# ModuleCarrier-MTS-Dragonfly.net
KiCad netlist of a schematic drawn in EAGLE
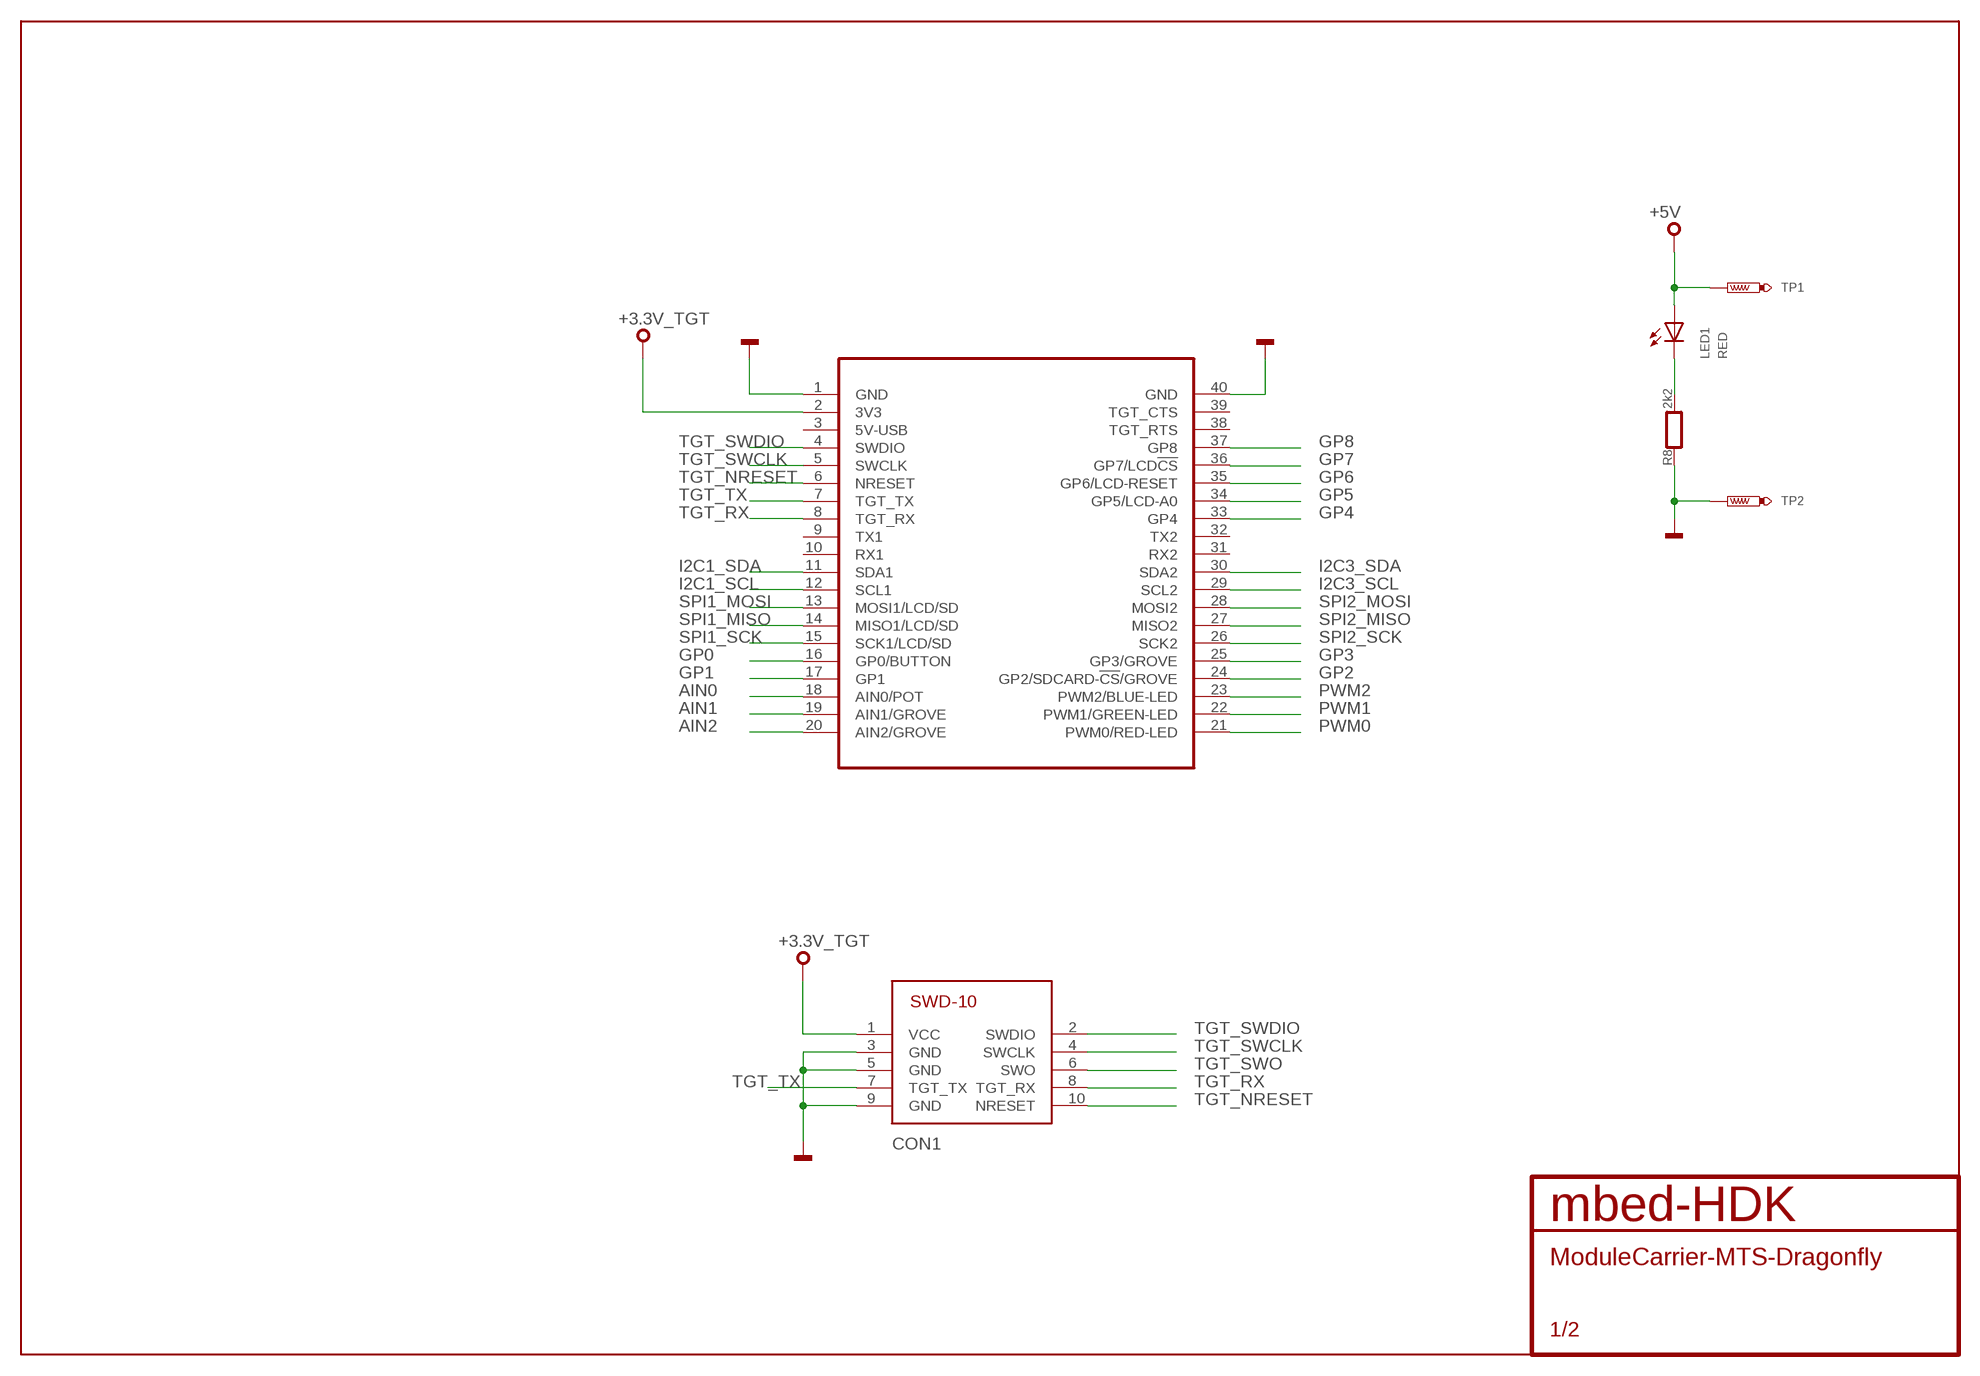
[diagram p0: schematic, sheet 1]
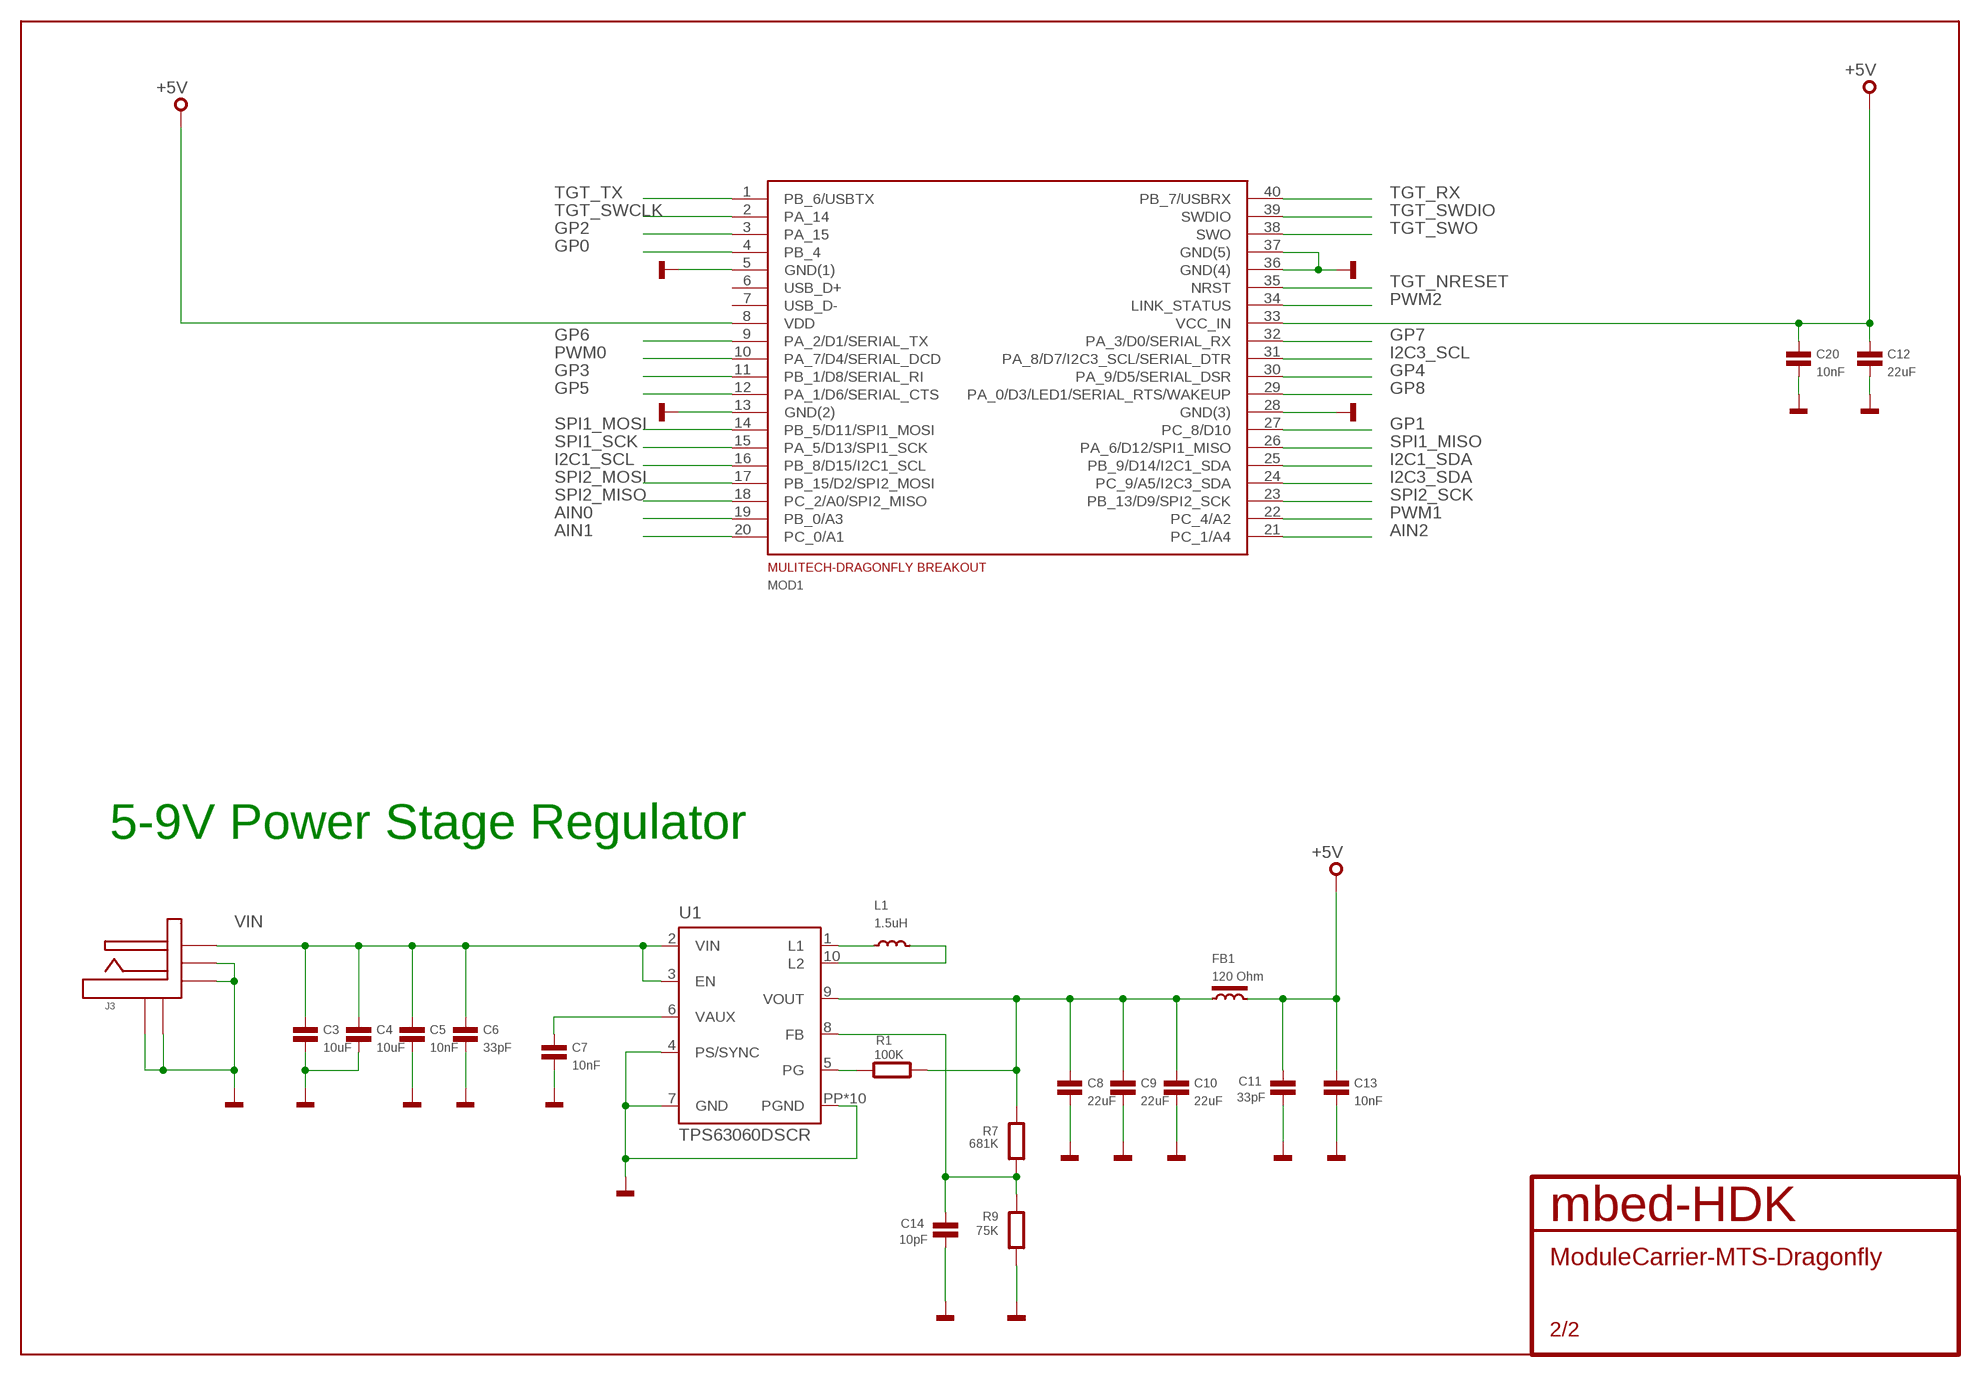
[diagram p1: schematic, sheet 2]

(export (version "E")
  (design (tool "Eeschema 10.0.6"))
  (components
    (comp (ref "C3")
      (value "10uF")
      (footprint "eagle-import:0603")
      (libsource (lib "eagle-import") (part "CAPACITOR0603"))
    )
    (comp (ref "C4")
      (value "10uF")
      (footprint "eagle-import:0603")
      (libsource (lib "eagle-import") (part "CAPACITOR0603"))
    )
    (comp (ref "C5")
      (value "10nF")
      (footprint "eagle-import:0603")
      (libsource (lib "eagle-import") (part "CAPACITOR0603"))
    )
    (comp (ref "C6")
      (value "33pF")
      (footprint "eagle-import:0603")
      (libsource (lib "eagle-import") (part "CAPACITOR0603"))
    )
    (comp (ref "C7")
      (value "10nF")
      (footprint "eagle-import:0603")
      (libsource (lib "eagle-import") (part "CAPACITOR0603"))
    )
    (comp (ref "C8")
      (value "22uF")
      (footprint "eagle-import:0603")
      (libsource (lib "eagle-import") (part "CAPACITOR0603"))
    )
    (comp (ref "C9")
      (value "22uF")
      (footprint "eagle-import:0603")
      (libsource (lib "eagle-import") (part "CAPACITOR0603"))
    )
    (comp (ref "C10")
      (value "22uF")
      (footprint "eagle-import:0603")
      (libsource (lib "eagle-import") (part "CAPACITOR0603"))
    )
    (comp (ref "C11")
      (value "33pF")
      (footprint "eagle-import:0603")
      (libsource (lib "eagle-import") (part "CAPACITOR0603"))
    )
    (comp (ref "C12")
      (value "22uF")
      (footprint "eagle-import:0603")
      (libsource (lib "eagle-import") (part "CAPACITOR0603"))
    )
    (comp (ref "C13")
      (value "10nF")
      (footprint "eagle-import:0603")
      (libsource (lib "eagle-import") (part "CAPACITOR0603"))
    )
    (comp (ref "C14")
      (value "10pF")
      (footprint "eagle-import:0603")
      (libsource (lib "eagle-import") (part "CAPACITOR0603"))
    )
    (comp (ref "C20")
      (value "10nF")
      (footprint "eagle-import:0603")
      (libsource (lib "eagle-import") (part "CAPACITOR0603"))
    )
    (comp (ref "FB1")
      (value "120 Ohm")
      (footprint "eagle-import:0603")
      (libsource (lib "eagle-import") (part "FERRITE0603"))
    )
    (comp (ref "J3")
      (value "FC68145S")
      (footprint "eagle-import:FC68145S")
      (libsource (lib "eagle-import") (part "FC68145S"))
    )
    (comp (ref "L1")
      (value "1.5uH")
      (footprint "eagle-import:XFL4020-472MEC")
      (libsource (lib "eagle-import") (part "INDUCTORXFL4020"))
    )
    (comp (ref "MOD1")
      (value "MULITECH-DRAGONFLY-BREAKOUT")
      (footprint "eagle-import:MULITECH-DRAGONFLY-BREAKOUT")
      (fields (field (name "MF") "Hirose"))
      (libsource (lib "eagle-import") (part "MULITECH-DRAGONFLY-BREAKOUT"))
    )
    (comp (ref "R1")
      (value "100K")
      (footprint "eagle-import:0402")
      (libsource (lib "eagle-import") (part "mbed-HDK-RLCQ_RESISTOR0402"))
    )
    (comp (ref "R7")
      (value "681K")
      (footprint "eagle-import:0402")
      (libsource (lib "eagle-import") (part "mbed-HDK-RLCQ_RESISTOR0402"))
    )
    (comp (ref "R9")
      (value "75K")
      (footprint "eagle-import:0402")
      (libsource (lib "eagle-import") (part "mbed-HDK-RLCQ_RESISTOR0402"))
    )
    (comp (ref "U1")
      (value "TPS63060DSCR")
      (footprint "eagle-import:DSC-S-PWSON-N10")
      (fields (field (name "MF") "TEXAS INSTRUMENTS"))
      (libsource (lib "eagle-import") (part "TPS63060DSCR"))
    )
    (comp (ref "CON1")
      (value "SWD-10/TC2050_SMD")
      (footprint "eagle-import:FTSH-105-02")
      (libsource (lib "eagle-import") (part "SWD-10/TC2050_SMD"))
    )
    (comp (ref "LED1")
      (value "RED")
      (footprint "eagle-import:CHIPLED_0603")
      (fields (field (name "MF") "Wurth Electronics Inc"))
      (libsource (lib "eagle-import") (part "SMD_LED0603"))
    )
    (comp (ref "MOD2")
      (value "MODULE_DAUGHTER")
      (footprint "eagle-import:MODULE_DAUGHTER")
      (libsource (lib "eagle-import") (part "MODULE_DAUGHTER"))
    )
    (comp (ref "R8")
      (value "2k2")
      (footprint "eagle-import:0603")
      (libsource (lib "eagle-import") (part "RESISTOR0603"))
    )
    (comp (ref "TP1")
      (value "TEST-POINT-50R-PTH")
      (footprint "eagle-import:TP50-PTH")
      (libsource (lib "eagle-import") (part "TEST-POINT-50R-PTH"))
    )
    (comp (ref "TP2")
      (value "TEST-POINT-50R-PTH")
      (footprint "eagle-import:TP50-PTH")
      (libsource (lib "eagle-import") (part "TEST-POINT-50R-PTH"))
    )
  )
  (nets
    (net (code "1") (name "+3.3V_TGT") (class "Default")
      (node (ref "CON1") (pin "1") (pinfunction "VCC_1") (pintype "bidirectional"))
      (node (ref "MOD2") (pin "2") (pinfunction "3V3_2") (pintype "bidirectional"))
    )
    (net (code "2") (name "+5V") (class "Default")
      (node (ref "C11") (pin "1") (pinfunction "P$1_1") (pintype "passive"))
      (node (ref "C12") (pin "1") (pinfunction "P$1_1") (pintype "passive"))
      (node (ref "C13") (pin "1") (pinfunction "P$1_1") (pintype "passive"))
      (node (ref "C20") (pin "1") (pinfunction "P$1_1") (pintype "passive"))
      (node (ref "FB1") (pin "2") (pinfunction "P$2_2") (pintype "bidirectional"))
      (node (ref "LED1") (pin "A") (pinfunction "A_A") (pintype "passive"))
      (node (ref "MOD1") (pin "33") (pinfunction "VCC_IN_33") (pintype "bidirectional"))
      (node (ref "MOD1") (pin "8") (pinfunction "VDD_8") (pintype "bidirectional"))
      (node (ref "TP1") (pin "TP") (pinfunction "TP_TP") (pintype "input"))
    )
    (net (code "3") (name "AIN0") (class "Default")
      (node (ref "MOD1") (pin "19") (pinfunction "PB_0/A3_19") (pintype "bidirectional"))
      (node (ref "MOD2") (pin "18") (pinfunction "AIN0/POT_18") (pintype "bidirectional"))
    )
    (net (code "4") (name "AIN1") (class "Default")
      (node (ref "MOD1") (pin "20") (pinfunction "PC_0/A1_20") (pintype "bidirectional"))
      (node (ref "MOD2") (pin "19") (pinfunction "AIN1/GROVE_19") (pintype "bidirectional"))
    )
    (net (code "5") (name "AIN2") (class "Default")
      (node (ref "MOD1") (pin "21") (pinfunction "PC_1/A4_21") (pintype "bidirectional"))
      (node (ref "MOD2") (pin "20") (pinfunction "AIN2/GROVE_20") (pintype "bidirectional"))
    )
    (net (code "6") (name "GND") (class "Default")
      (node (ref "C10") (pin "2") (pinfunction "P$2_2") (pintype "passive"))
      (node (ref "C11") (pin "2") (pinfunction "P$2_2") (pintype "passive"))
      (node (ref "C12") (pin "2") (pinfunction "P$2_2") (pintype "passive"))
      (node (ref "C13") (pin "2") (pinfunction "P$2_2") (pintype "passive"))
      (node (ref "C14") (pin "2") (pinfunction "P$2_2") (pintype "passive"))
      (node (ref "C20") (pin "2") (pinfunction "P$2_2") (pintype "passive"))
      (node (ref "C3") (pin "2") (pinfunction "P$2_2") (pintype "passive"))
      (node (ref "C4") (pin "2") (pinfunction "P$2_2") (pintype "passive"))
      (node (ref "C5") (pin "2") (pinfunction "P$2_2") (pintype "passive"))
      (node (ref "C6") (pin "2") (pinfunction "P$2_2") (pintype "passive"))
      (node (ref "C7") (pin "2") (pinfunction "P$2_2") (pintype "passive"))
      (node (ref "C8") (pin "2") (pinfunction "P$2_2") (pintype "passive"))
      (node (ref "C9") (pin "2") (pinfunction "P$2_2") (pintype "passive"))
      (node (ref "CON1") (pin "3") (pinfunction "GND_3") (pintype "bidirectional"))
      (node (ref "CON1") (pin "5") (pinfunction "GND_5") (pintype "bidirectional"))
      (node (ref "CON1") (pin "9") (pinfunction "GND_9") (pintype "bidirectional"))
      (node (ref "J3") (pin "CASE1") (pinfunction "CASE1_CASE1") (pintype "bidirectional"))
      (node (ref "J3") (pin "P$5") (pinfunction "CASE2_P$5") (pintype "bidirectional"))
      (node (ref "J3") (pin "SHUNT") (pinfunction "SWITCHED_SHUNT") (pintype "bidirectional"))
      (node (ref "J3") (pin "SLEEVE") (pinfunction "SLEEVE_SLEEVE") (pintype "bidirectional"))
      (node (ref "MOD1") (pin "13") (pinfunction "GND(2)_13") (pintype "bidirectional"))
      (node (ref "MOD1") (pin "28") (pinfunction "GND(3)_28") (pintype "bidirectional"))
      (node (ref "MOD1") (pin "36") (pinfunction "GND(4)_36") (pintype "bidirectional"))
      (node (ref "MOD1") (pin "37") (pinfunction "GND(5)_37") (pintype "bidirectional"))
      (node (ref "MOD1") (pin "5") (pinfunction "GND(1)_5") (pintype "bidirectional"))
      (node (ref "MOD2") (pin "1") (pinfunction "GND_1") (pintype "bidirectional"))
      (node (ref "MOD2") (pin "40") (pinfunction "GND_40") (pintype "bidirectional"))
      (node (ref "R8") (pin "1") (pinfunction "P$1_1") (pintype "passive"))
      (node (ref "R9") (pin "1") (pinfunction "P$1_1") (pintype "passive"))
      (node (ref "TP2") (pin "TP") (pinfunction "TP_TP") (pintype "input"))
      (node (ref "U1") (pin "4") (pinfunction "PS/SYNC_4") (pintype "input"))
      (node (ref "U1") (pin "7") (pinfunction "GND_7") (pintype "input"))
      (node (ref "U1") (pin "PP") (pinfunction "PGND_PP") (pintype "power_in"))
      (node (ref "U1") (pin "PP@1") (pinfunction "PGND_PP@1") (pintype "power_in"))
      (node (ref "U1") (pin "PP@10") (pinfunction "PGND_PP@10") (pintype "power_in"))
      (node (ref "U1") (pin "PP@2") (pinfunction "PGND_PP@2") (pintype "power_in"))
      (node (ref "U1") (pin "PP@3") (pinfunction "PGND_PP@3") (pintype "power_in"))
      (node (ref "U1") (pin "PP@4") (pinfunction "PGND_PP@4") (pintype "power_in"))
      (node (ref "U1") (pin "PP@5") (pinfunction "PGND_PP@5") (pintype "power_in"))
      (node (ref "U1") (pin "PP@7") (pinfunction "PGND_PP@7") (pintype "power_in"))
      (node (ref "U1") (pin "PP@8") (pinfunction "PGND_PP@8") (pintype "power_in"))
      (node (ref "U1") (pin "PP@9") (pinfunction "PGND_PP@9") (pintype "power_in"))
    )
    (net (code "7") (name "GP0") (class "Default")
      (node (ref "MOD1") (pin "4") (pinfunction "PB_4_4") (pintype "bidirectional"))
      (node (ref "MOD2") (pin "16") (pinfunction "GP0/BUTTON_16") (pintype "bidirectional"))
    )
    (net (code "8") (name "GP1") (class "Default")
      (node (ref "MOD1") (pin "27") (pinfunction "PC_8/D10_27") (pintype "bidirectional"))
      (node (ref "MOD2") (pin "17") (pinfunction "GP1_17") (pintype "bidirectional"))
    )
    (net (code "9") (name "GP2") (class "Default")
      (node (ref "MOD1") (pin "3") (pinfunction "PA_15_3") (pintype "bidirectional"))
      (node (ref "MOD2") (pin "24") (pinfunction "GP2/SDCARD-~{CS}/GROVE_24") (pintype "bidirectional"))
    )
    (net (code "10") (name "GP3") (class "Default")
      (node (ref "MOD1") (pin "11") (pinfunction "PB_1/D8/SERIAL_RI_11") (pintype "bidirectional"))
      (node (ref "MOD2") (pin "25") (pinfunction "GP3/GROVE_25") (pintype "bidirectional"))
    )
    (net (code "11") (name "GP4") (class "Default")
      (node (ref "MOD1") (pin "30") (pinfunction "PA_9/D5/SERIAL_DSR_30") (pintype "bidirectional"))
      (node (ref "MOD2") (pin "33") (pinfunction "GP4_33") (pintype "bidirectional"))
    )
    (net (code "12") (name "GP5") (class "Default")
      (node (ref "MOD1") (pin "12") (pinfunction "PA_1/D6/SERIAL_CTS_12") (pintype "bidirectional"))
      (node (ref "MOD2") (pin "34") (pinfunction "GP5/LCD-A0_34") (pintype "bidirectional"))
    )
    (net (code "13") (name "GP6") (class "Default")
      (node (ref "MOD1") (pin "9") (pinfunction "PA_2/D1/SERIAL_TX_9") (pintype "bidirectional"))
      (node (ref "MOD2") (pin "35") (pinfunction "GP6/LCD-RESET_35") (pintype "bidirectional"))
    )
    (net (code "14") (name "GP7") (class "Default")
      (node (ref "MOD1") (pin "32") (pinfunction "PA_3/D0/SERIAL_RX_32") (pintype "bidirectional"))
      (node (ref "MOD2") (pin "36") (pinfunction "GP7/LCD~{CS}_36") (pintype "bidirectional"))
    )
    (net (code "15") (name "GP8") (class "Default")
      (node (ref "MOD1") (pin "29") (pinfunction "PA_0/D3/LED1/SERIAL_RTS/WAKEUP_29") (pintype "bidirectional"))
      (node (ref "MOD2") (pin "37") (pinfunction "GP8_37") (pintype "bidirectional"))
    )
    (net (code "16") (name "I2C1_SCL") (class "Default")
      (node (ref "MOD1") (pin "16") (pinfunction "PB_8/D15/I2C1_SCL_16") (pintype "bidirectional"))
      (node (ref "MOD2") (pin "12") (pinfunction "SCL1_12") (pintype "bidirectional"))
    )
    (net (code "17") (name "I2C1_SDA") (class "Default")
      (node (ref "MOD1") (pin "25") (pinfunction "PB_9/D14/I2C1_SDA_25") (pintype "bidirectional"))
      (node (ref "MOD2") (pin "11") (pinfunction "SDA1_11") (pintype "bidirectional"))
    )
    (net (code "18") (name "I2C3_SCL") (class "Default")
      (node (ref "MOD1") (pin "31") (pinfunction "PA_8/D7/I2C3_SCL/SERIAL_DTR_31") (pintype "bidirectional"))
      (node (ref "MOD2") (pin "29") (pinfunction "SCL2_29") (pintype "bidirectional"))
    )
    (net (code "19") (name "I2C3_SDA") (class "Default")
      (node (ref "MOD1") (pin "24") (pinfunction "PC_9/A5/I2C3_SDA_24") (pintype "bidirectional"))
      (node (ref "MOD2") (pin "30") (pinfunction "SDA2_30") (pintype "bidirectional"))
    )
    (net (code "20") (name "Net-(C7-P$1)") (class "Default")
      (node (ref "C7") (pin "1") (pinfunction "P$1_1") (pintype "passive"))
      (node (ref "U1") (pin "6") (pinfunction "VAUX_6") (pintype "power_in"))
    )
    (net (code "21") (name "Net-(C10-P$1)") (class "Default")
      (node (ref "C10") (pin "1") (pinfunction "P$1_1") (pintype "passive"))
      (node (ref "C8") (pin "1") (pinfunction "P$1_1") (pintype "passive"))
      (node (ref "C9") (pin "1") (pinfunction "P$1_1") (pintype "passive"))
      (node (ref "FB1") (pin "1") (pinfunction "P$1_1") (pintype "bidirectional"))
      (node (ref "R1") (pin "2") (pinfunction "P$2_2") (pintype "passive"))
      (node (ref "R7") (pin "2") (pinfunction "P$2_2") (pintype "passive"))
      (node (ref "U1") (pin "9") (pinfunction "VOUT_9") (pintype "output"))
    )
    (net (code "22") (name "Net-(C14-P$1)") (class "Default")
      (node (ref "C14") (pin "1") (pinfunction "P$1_1") (pintype "passive"))
      (node (ref "R7") (pin "1") (pinfunction "P$1_1") (pintype "passive"))
      (node (ref "R9") (pin "2") (pinfunction "P$2_2") (pintype "passive"))
      (node (ref "U1") (pin "8") (pinfunction "FB_8") (pintype "input"))
    )
    (net (code "23") (name "Net-(R1-P$1)") (class "Default")
      (node (ref "R1") (pin "1") (pinfunction "P$1_1") (pintype "passive"))
      (node (ref "U1") (pin "5") (pinfunction "PG_5") (pintype "output"))
    )
    (net (code "24") (name "Net-(R8-P$2)") (class "Default")
      (node (ref "LED1") (pin "C") (pinfunction "C_C") (pintype "passive"))
      (node (ref "R8") (pin "2") (pinfunction "P$2_2") (pintype "passive"))
    )
    (net (code "25") (name "Net-(U1-L1)") (class "Default")
      (node (ref "L1") (pin "P$1") (pinfunction "P$1_P$1") (pintype "bidirectional"))
      (node (ref "U1") (pin "1") (pinfunction "L1_1") (pintype "input"))
    )
    (net (code "26") (name "Net-(U1-L2)") (class "Default")
      (node (ref "L1") (pin "P$2") (pinfunction "P$2_P$2") (pintype "bidirectional"))
      (node (ref "U1") (pin "10") (pinfunction "L2_10") (pintype "input"))
    )
    (net (code "27") (name "PWM0") (class "Default")
      (node (ref "MOD1") (pin "10") (pinfunction "PA_7/D4/SERIAL_DCD_10") (pintype "bidirectional"))
      (node (ref "MOD2") (pin "21") (pinfunction "PWM0/RED-LED_21") (pintype "bidirectional"))
    )
    (net (code "28") (name "PWM1") (class "Default")
      (node (ref "MOD1") (pin "22") (pinfunction "PC_4/A2_22") (pintype "bidirectional"))
      (node (ref "MOD2") (pin "22") (pinfunction "PWM1/GREEN-LED_22") (pintype "bidirectional"))
    )
    (net (code "29") (name "PWM2") (class "Default")
      (node (ref "MOD1") (pin "34") (pinfunction "LINK_STATUS_34") (pintype "bidirectional"))
      (node (ref "MOD2") (pin "23") (pinfunction "PWM2/BLUE-LED_23") (pintype "bidirectional"))
    )
    (net (code "30") (name "SPI1_MISO") (class "Default")
      (node (ref "MOD1") (pin "26") (pinfunction "PA_6/D12/SPI1_MISO_26") (pintype "bidirectional"))
      (node (ref "MOD2") (pin "14") (pinfunction "MISO1/LCD/SD_14") (pintype "bidirectional"))
    )
    (net (code "31") (name "SPI1_MOSI") (class "Default")
      (node (ref "MOD1") (pin "14") (pinfunction "PB_5/D11/SPI1_MOSI_14") (pintype "bidirectional"))
      (node (ref "MOD2") (pin "13") (pinfunction "MOSI1/LCD/SD_13") (pintype "bidirectional"))
    )
    (net (code "32") (name "SPI1_SCK") (class "Default")
      (node (ref "MOD1") (pin "15") (pinfunction "PA_5/D13/SPI1_SCK_15") (pintype "bidirectional"))
      (node (ref "MOD2") (pin "15") (pinfunction "SCK1/LCD/SD_15") (pintype "bidirectional"))
    )
    (net (code "33") (name "SPI2_MISO") (class "Default")
      (node (ref "MOD1") (pin "18") (pinfunction "PC_2/A0/SPI2_MISO_18") (pintype "bidirectional"))
      (node (ref "MOD2") (pin "27") (pinfunction "MISO2_27") (pintype "bidirectional"))
    )
    (net (code "34") (name "SPI2_MOSI") (class "Default")
      (node (ref "MOD1") (pin "17") (pinfunction "PB_15/D2/SPI2_MOSI_17") (pintype "bidirectional"))
      (node (ref "MOD2") (pin "28") (pinfunction "MOSI2_28") (pintype "bidirectional"))
    )
    (net (code "35") (name "SPI2_SCK") (class "Default")
      (node (ref "MOD1") (pin "23") (pinfunction "PB_13/D9/SPI2_SCK_23") (pintype "bidirectional"))
      (node (ref "MOD2") (pin "26") (pinfunction "SCK2_26") (pintype "bidirectional"))
    )
    (net (code "36") (name "TGT_NRESET") (class "Default")
      (node (ref "CON1") (pin "10") (pinfunction "NRESET_10") (pintype "bidirectional"))
      (node (ref "MOD1") (pin "35") (pinfunction "NRST_35") (pintype "bidirectional"))
      (node (ref "MOD2") (pin "6") (pinfunction "NRESET_6") (pintype "bidirectional"))
    )
    (net (code "37") (name "TGT_RX") (class "Default")
      (node (ref "CON1") (pin "8") (pinfunction "TGT_RX_8") (pintype "bidirectional"))
      (node (ref "MOD1") (pin "40") (pinfunction "PB_7/USBRX_40") (pintype "bidirectional"))
      (node (ref "MOD2") (pin "8") (pinfunction "TGT_RX_8") (pintype "bidirectional"))
    )
    (net (code "38") (name "TGT_SWCLK") (class "Default")
      (node (ref "CON1") (pin "4") (pinfunction "SWCLK_4") (pintype "bidirectional"))
      (node (ref "MOD1") (pin "2") (pinfunction "PA_14_2") (pintype "bidirectional"))
      (node (ref "MOD2") (pin "5") (pinfunction "SWCLK_5") (pintype "bidirectional"))
    )
    (net (code "39") (name "TGT_SWDIO") (class "Default")
      (node (ref "CON1") (pin "2") (pinfunction "SWDIO_2") (pintype "bidirectional"))
      (node (ref "MOD1") (pin "39") (pinfunction "SWDIO_39") (pintype "bidirectional"))
      (node (ref "MOD2") (pin "4") (pinfunction "SWDIO_4") (pintype "bidirectional"))
    )
    (net (code "40") (name "TGT_SWO") (class "Default")
      (node (ref "CON1") (pin "6") (pinfunction "SWO_6") (pintype "bidirectional"))
      (node (ref "MOD1") (pin "38") (pinfunction "SWO_38") (pintype "bidirectional"))
    )
    (net (code "41") (name "TGT_TX") (class "Default")
      (node (ref "CON1") (pin "7") (pinfunction "TGT_TX_7") (pintype "bidirectional"))
      (node (ref "MOD1") (pin "1") (pinfunction "PB_6/USBTX_1") (pintype "bidirectional"))
      (node (ref "MOD2") (pin "7") (pinfunction "TGT_TX_7") (pintype "bidirectional"))
    )
    (net (code "42") (name "VIN") (class "Default")
      (node (ref "C3") (pin "1") (pinfunction "P$1_1") (pintype "passive"))
      (node (ref "C4") (pin "1") (pinfunction "P$1_1") (pintype "passive"))
      (node (ref "C5") (pin "1") (pinfunction "P$1_1") (pintype "passive"))
      (node (ref "C6") (pin "1") (pinfunction "P$1_1") (pintype "passive"))
      (node (ref "J3") (pin "TIP") (pinfunction "TIP_TIP") (pintype "bidirectional"))
      (node (ref "U1") (pin "2") (pinfunction "VIN_2") (pintype "input"))
      (node (ref "U1") (pin "3") (pinfunction "EN_3") (pintype "input"))
    )
    (net (code "43") (name "unconnected-(MOD1-USB_D+-Pad6)") (class "Default")
      (node (ref "MOD1") (pin "6") (pinfunction "USB_D+_6") (pintype "bidirectional"))
    )
    (net (code "44") (name "unconnected-(MOD1-USB_D--Pad7)") (class "Default")
      (node (ref "MOD1") (pin "7") (pinfunction "USB_D-_7") (pintype "bidirectional"))
    )
    (net (code "45") (name "unconnected-(MOD2-5V-USB-Pad3)") (class "Default")
      (node (ref "MOD2") (pin "3") (pinfunction "5V-USB_3") (pintype "bidirectional"))
    )
    (net (code "46") (name "unconnected-(MOD2-RX1-Pad10)") (class "Default")
      (node (ref "MOD2") (pin "10") (pinfunction "RX1_10") (pintype "bidirectional"))
    )
    (net (code "47") (name "unconnected-(MOD2-RX2-Pad31)") (class "Default")
      (node (ref "MOD2") (pin "31") (pinfunction "RX2_31") (pintype "bidirectional"))
    )
    (net (code "48") (name "unconnected-(MOD2-TGT_CTS-Pad39)") (class "Default")
      (node (ref "MOD2") (pin "39") (pinfunction "TGT_CTS_39") (pintype "bidirectional"))
    )
    (net (code "49") (name "unconnected-(MOD2-TGT_RTS-Pad38)") (class "Default")
      (node (ref "MOD2") (pin "38") (pinfunction "TGT_RTS_38") (pintype "bidirectional"))
    )
    (net (code "50") (name "unconnected-(MOD2-TX1-Pad9)") (class "Default")
      (node (ref "MOD2") (pin "9") (pinfunction "TX1_9") (pintype "bidirectional"))
    )
    (net (code "51") (name "unconnected-(MOD2-TX2-Pad32)") (class "Default")
      (node (ref "MOD2") (pin "32") (pinfunction "TX2_32") (pintype "bidirectional"))
    )
  )
)
